# 00A-93.net
KiCad netlist of a schematic drawn in EAGLE
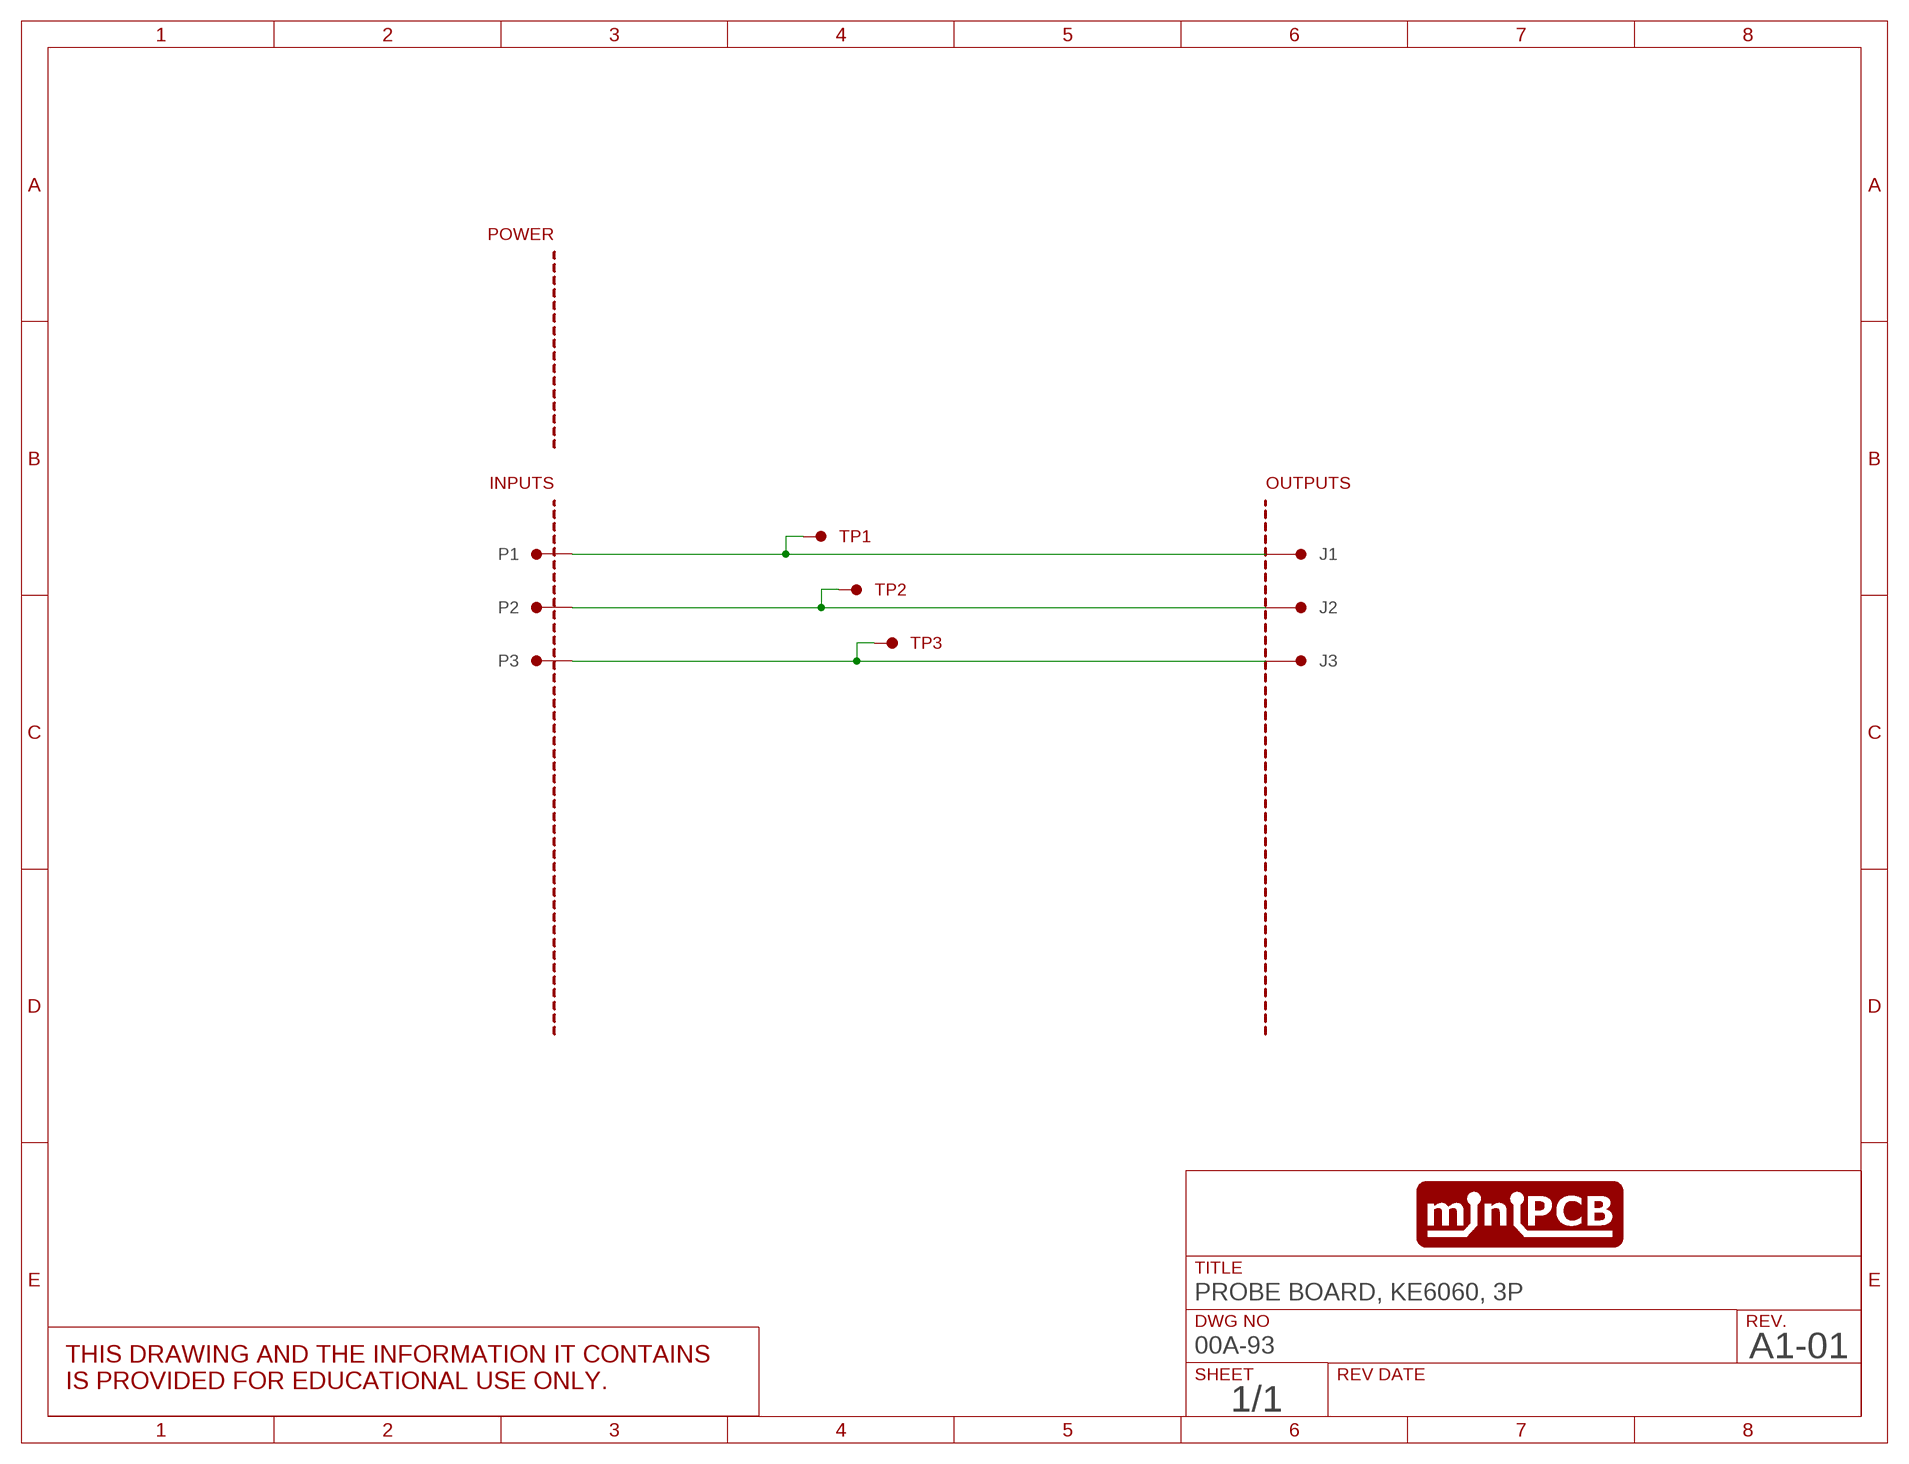
[diagram p0: schematic, sheet 1]

(export (version "E")
  (design (tool "Eeschema 10.0.6"))
  (components
    (comp (ref "J1")
      (value "PINS_1KE6060")
      (footprint "eagle-import:PINS_1_KE6060")
      (libsource (lib "eagle-import") (part "PINS_1KE6060"))
    )
    (comp (ref "J2")
      (value "PINS_1KE6060")
      (footprint "eagle-import:PINS_1_KE6060")
      (libsource (lib "eagle-import") (part "PINS_1KE6060"))
    )
    (comp (ref "J3")
      (value "PINS_1KE6060")
      (footprint "eagle-import:PINS_1_KE6060")
      (libsource (lib "eagle-import") (part "PINS_1KE6060"))
    )
    (comp (ref "P1")
      (value "PINS_124AWG-NOTEXT")
      (footprint "eagle-import:PINS_1_1MM-NOTEXT")
      (libsource (lib "eagle-import") (part "PINS_124AWG-NOTEXT"))
    )
    (comp (ref "P2")
      (value "PINS_124AWG-NOTEXT")
      (footprint "eagle-import:PINS_1_1MM-NOTEXT")
      (libsource (lib "eagle-import") (part "PINS_124AWG-NOTEXT"))
    )
    (comp (ref "P3")
      (value "PINS_124AWG-NOTEXT")
      (footprint "eagle-import:PINS_1_1MM-NOTEXT")
      (libsource (lib "eagle-import") (part "PINS_124AWG-NOTEXT"))
    )
    (comp (ref "PCB1")
      (value "MINIPCB_0P00A-20X50")
      (footprint "eagle-import:MINIPCB_00A_20X50")
      (fields (field (name "PART_NUMBER") "00A-93-A1-01"))
      (libsource (lib "eagle-import") (part "MINIPCB_0P00A-20X50"))
    )
    (comp (ref "TP1")
      (value "TESTPOINTKE5000-SMTEXT")
      (footprint "eagle-import:PINS_1_TESTPOINT_KE5000_NOTEXT")
      (libsource (lib "eagle-import") (part "TESTPOINTKE5000-SMTEXT"))
    )
    (comp (ref "TP2")
      (value "TESTPOINTKE5000-SMTEXT")
      (footprint "eagle-import:PINS_1_TESTPOINT_KE5000_NOTEXT")
      (libsource (lib "eagle-import") (part "TESTPOINTKE5000-SMTEXT"))
    )
    (comp (ref "TP3")
      (value "TESTPOINTKE5000-SMTEXT")
      (footprint "eagle-import:PINS_1_TESTPOINT_KE5000_NOTEXT")
      (libsource (lib "eagle-import") (part "TESTPOINTKE5000-SMTEXT"))
    )
  )
  (nets
    (net (code "1") (name "Net-(J1-1-Pad2)") (class "Default")
      (node (ref "J1") (pin "1") (pinfunction "1_1") (pintype "bidirectional"))
      (node (ref "J1") (pin "2") (pinfunction "1_2") (pintype "bidirectional"))
      (node (ref "P1") (pin "1") (pinfunction "1_1") (pintype "bidirectional"))
      (node (ref "P1") (pin "2") (pinfunction "1_2") (pintype "bidirectional"))
      (node (ref "TP1") (pin "1") (pinfunction "1_1") (pintype "bidirectional"))
    )
    (net (code "2") (name "Net-(J2-1-Pad2)") (class "Default")
      (node (ref "J2") (pin "1") (pinfunction "1_1") (pintype "bidirectional"))
      (node (ref "J2") (pin "2") (pinfunction "1_2") (pintype "bidirectional"))
      (node (ref "P2") (pin "1") (pinfunction "1_1") (pintype "bidirectional"))
      (node (ref "P2") (pin "2") (pinfunction "1_2") (pintype "bidirectional"))
      (node (ref "TP2") (pin "1") (pinfunction "1_1") (pintype "bidirectional"))
    )
    (net (code "3") (name "Net-(J3-1-Pad2)") (class "Default")
      (node (ref "J3") (pin "1") (pinfunction "1_1") (pintype "bidirectional"))
      (node (ref "J3") (pin "2") (pinfunction "1_2") (pintype "bidirectional"))
      (node (ref "P3") (pin "1") (pinfunction "1_1") (pintype "bidirectional"))
      (node (ref "P3") (pin "2") (pinfunction "1_2") (pintype "bidirectional"))
      (node (ref "TP3") (pin "1") (pinfunction "1_1") (pintype "bidirectional"))
    )
  )
)
